# Gimbal_Power.net
KiCad netlist of a schematic drawn in Altium Designer
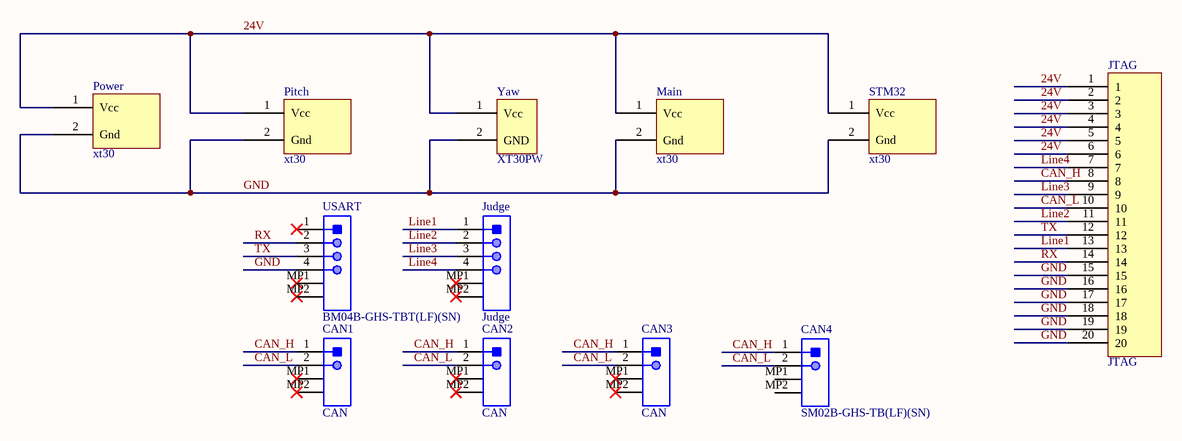
[diagram p0: Gimbal_Power.SchDoc]

(export (version "E")
  (design (tool "Eeschema 10.0.6"))
  (components
    (comp (ref "CAN1")
      (value "CAN")
      (footprint "JST-SM02B-GHS-TB_V")
      (fields (field (name "MANUFACTURER") "JST"))
      (libsource (lib "Integrated_Library1") (part "SM02B-GHS-TB(LF)(SN)"))
    )
    (comp (ref "CAN2")
      (value "CAN")
      (footprint "JST-BM02B-GHS-TBT_V")
      (fields (field (name "MANUFACTURER") "JST"))
      (libsource (lib "Integrated_Library1") (part "BM02B-GHS-TBT(LF)(SN)"))
    )
    (comp (ref "CAN3")
      (value "CAN")
      (footprint "JST-BM02B-GHS-TBT_V")
      (fields (field (name "MANUFACTURER") "JST"))
      (libsource (lib "Integrated_Library1") (part "BM02B-GHS-TBT(LF)(SN)"))
    )
    (comp (ref "CAN4")
      (value "SM02B-GHS-TB(LF)(SN)")
      (footprint "JST-SM02B-GHS-TB_V")
      (fields (field (name "MANUFACTURER") "JST"))
      (libsource (lib "Integrated_Library1") (part "SM02B-GHS-TB(LF)(SN)"))
    )
    (comp (ref "JTAG")
      (value "JTAG")
      (footprint "IDC20S")
      (libsource (lib "Integrated_Library1") (part "JTAG"))
    )
    (comp (ref "Judge")
      (value "Judge")
      (footprint "JST-BM04B-GHS-TBT_V")
      (fields (field (name "MANUFACTURER") "JST"))
      (libsource (lib "Integrated_Library1") (part "BM04B-GHS-TBT(LF)(SN)"))
    )
    (comp (ref "Main")
      (value "xt30")
      (footprint "XT30")
      (libsource (lib "Integrated_Library1") (part "xt30"))
    )
    (comp (ref "Pitch")
      (value "xt30")
      (footprint "XT30")
      (libsource (lib "Integrated_Library1") (part "xt30"))
    )
    (comp (ref "Power") (value "xt30") (footprint "XT30") (libsource (lib "RMlib1") (part "xt30")))
    (comp (ref "STM32")
      (value "xt30")
      (footprint "XT30")
      (libsource (lib "Integrated_Library1") (part "xt30"))
    )
    (comp (ref "USART")
      (value "BM04B-GHS-TBT(LF)(SN)")
      (footprint "JST-BM04B-GHS-TBT_V")
      (fields (field (name "MANUFACTURER") "JST"))
      (libsource (lib "JST GH connector") (part "BM04B-GHS-TBT(LF)(SN)"))
    )
    (comp (ref "Yaw")
      (value "XT30PW")
      (footprint "XT30PW")
      (libsource (lib "Integrated_Library1") (part "XT30PW"))
    )
  )
  (nets
    (net (code "1") (name "/24V") (class "Default")
      (node (ref "JTAG") (pin "1") (pinfunction "1_1") (pintype "passive"))
      (node (ref "JTAG") (pin "2") (pinfunction "2_2") (pintype "passive"))
      (node (ref "JTAG") (pin "3") (pinfunction "3_3") (pintype "passive"))
      (node (ref "JTAG") (pin "4") (pinfunction "4_4") (pintype "passive"))
      (node (ref "JTAG") (pin "5") (pinfunction "5_5") (pintype "passive"))
      (node (ref "JTAG") (pin "6") (pinfunction "6_6") (pintype "passive"))
      (node (ref "Main") (pin "1") (pinfunction "Vcc_1") (pintype "passive"))
      (node (ref "Pitch") (pin "1") (pinfunction "Vcc_1") (pintype "passive"))
      (node (ref "Power") (pin "1") (pinfunction "Vcc_1") (pintype "passive"))
      (node (ref "STM32") (pin "1") (pinfunction "Vcc_1") (pintype "passive"))
      (node (ref "Yaw") (pin "1") (pinfunction "Vcc_1") (pintype "passive"))
    )
    (net (code "2") (name "/CAN_H") (class "Default")
      (node (ref "CAN1") (pin "1") (pinfunction "1_1") (pintype "passive"))
      (node (ref "CAN2") (pin "1") (pinfunction "1_1") (pintype "passive"))
      (node (ref "CAN3") (pin "1") (pinfunction "1_1") (pintype "passive"))
      (node (ref "CAN4") (pin "1") (pinfunction "1_1") (pintype "passive"))
      (node (ref "JTAG") (pin "8") (pinfunction "8_8") (pintype "passive"))
    )
    (net (code "3") (name "/CAN_L") (class "Default")
      (node (ref "CAN1") (pin "2") (pinfunction "2_2") (pintype "passive"))
      (node (ref "CAN2") (pin "2") (pinfunction "2_2") (pintype "passive"))
      (node (ref "CAN3") (pin "2") (pinfunction "2_2") (pintype "passive"))
      (node (ref "CAN4") (pin "2") (pinfunction "2_2") (pintype "passive"))
      (node (ref "JTAG") (pin "10") (pinfunction "10_10") (pintype "passive"))
    )
    (net (code "4") (name "/GND") (class "Default")
      (node (ref "JTAG") (pin "15") (pinfunction "15_15") (pintype "passive"))
      (node (ref "JTAG") (pin "16") (pinfunction "16_16") (pintype "passive"))
      (node (ref "JTAG") (pin "17") (pinfunction "17_17") (pintype "passive"))
      (node (ref "JTAG") (pin "18") (pinfunction "18_18") (pintype "passive"))
      (node (ref "JTAG") (pin "19") (pinfunction "19_19") (pintype "passive"))
      (node (ref "JTAG") (pin "20") (pinfunction "20_20") (pintype "passive"))
      (node (ref "Main") (pin "2") (pinfunction "Gnd_2") (pintype "passive"))
      (node (ref "Pitch") (pin "2") (pinfunction "Gnd_2") (pintype "passive"))
      (node (ref "Power") (pin "2") (pinfunction "Gnd_2") (pintype "passive"))
      (node (ref "STM32") (pin "2") (pinfunction "Gnd_2") (pintype "passive"))
      (node (ref "USART") (pin "4") (pinfunction "4_4") (pintype "passive"))
      (node (ref "Yaw") (pin "2") (pinfunction "GND_2") (pintype "passive"))
    )
    (net (code "5") (name "/Line1") (class "Default")
      (node (ref "JTAG") (pin "13") (pinfunction "13_13") (pintype "passive"))
      (node (ref "Judge") (pin "1") (pinfunction "1_1") (pintype "passive"))
    )
    (net (code "6") (name "/Line2") (class "Default")
      (node (ref "JTAG") (pin "11") (pinfunction "11_11") (pintype "passive"))
      (node (ref "Judge") (pin "2") (pinfunction "2_2") (pintype "passive"))
    )
    (net (code "7") (name "/Line3") (class "Default")
      (node (ref "JTAG") (pin "9") (pinfunction "9_9") (pintype "passive"))
      (node (ref "Judge") (pin "3") (pinfunction "3_3") (pintype "passive"))
    )
    (net (code "8") (name "/Line4") (class "Default")
      (node (ref "JTAG") (pin "7") (pinfunction "7_7") (pintype "passive"))
      (node (ref "Judge") (pin "4") (pinfunction "4_4") (pintype "passive"))
    )
    (net (code "9") (name "/RX") (class "Default")
      (node (ref "JTAG") (pin "14") (pinfunction "14_14") (pintype "passive"))
      (node (ref "USART") (pin "2") (pinfunction "2_2") (pintype "passive"))
    )
    (net (code "10") (name "/TX") (class "Default")
      (node (ref "JTAG") (pin "12") (pinfunction "12_12") (pintype "passive"))
      (node (ref "USART") (pin "3") (pinfunction "3_3") (pintype "passive"))
    )
    (net (code "11") (name "unconnected-(CAN1-PadMP1)") (class "Default")
      (node (ref "CAN1") (pin "MP1") (pinfunction "MP1_MP1") (pintype "passive+no_connect"))
    )
    (net (code "12") (name "unconnected-(CAN1-PadMP2)") (class "Default")
      (node (ref "CAN1") (pin "MP2") (pinfunction "MP2_MP2") (pintype "passive+no_connect"))
    )
    (net (code "13") (name "unconnected-(CAN2-PadMP1)") (class "Default")
      (node (ref "CAN2") (pin "MP1") (pinfunction "MP1_MP1") (pintype "passive+no_connect"))
    )
    (net (code "14") (name "unconnected-(CAN2-PadMP2)") (class "Default")
      (node (ref "CAN2") (pin "MP2") (pinfunction "MP2_MP2") (pintype "passive+no_connect"))
    )
    (net (code "15") (name "unconnected-(CAN3-PadMP1)") (class "Default")
      (node (ref "CAN3") (pin "MP1") (pinfunction "MP1_MP1") (pintype "passive+no_connect"))
    )
    (net (code "16") (name "unconnected-(CAN3-PadMP2)") (class "Default")
      (node (ref "CAN3") (pin "MP2") (pinfunction "MP2_MP2") (pintype "passive+no_connect"))
    )
    (net (code "17") (name "unconnected-(CAN4-PadMP1)") (class "Default")
      (node (ref "CAN4") (pin "MP1") (pinfunction "MP1_MP1") (pintype "passive"))
    )
    (net (code "18") (name "unconnected-(CAN4-PadMP2)") (class "Default")
      (node (ref "CAN4") (pin "MP2") (pinfunction "MP2_MP2") (pintype "passive"))
    )
    (net (code "19") (name "unconnected-(Judge-PadMP1)") (class "Default")
      (node (ref "Judge") (pin "MP1") (pinfunction "MP1_MP1") (pintype "passive+no_connect"))
    )
    (net (code "20") (name "unconnected-(Judge-PadMP2)") (class "Default")
      (node (ref "Judge") (pin "MP2") (pinfunction "MP2_MP2") (pintype "passive+no_connect"))
    )
    (net (code "21") (name "unconnected-(USART-Pad1)") (class "Default")
      (node (ref "USART") (pin "1") (pinfunction "1_1") (pintype "passive+no_connect"))
    )
    (net (code "22") (name "unconnected-(USART-PadMP1)") (class "Default")
      (node (ref "USART") (pin "MP1") (pinfunction "MP1_MP1") (pintype "passive+no_connect"))
    )
    (net (code "23") (name "unconnected-(USART-PadMP2)") (class "Default")
      (node (ref "USART") (pin "MP2") (pinfunction "MP2_MP2") (pintype "passive+no_connect"))
    )
  )
)
